# StepStick.net
KiCad netlist of a schematic drawn in Altium Designer
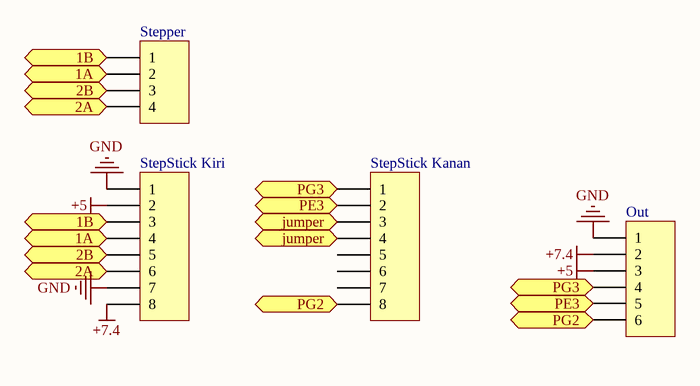
[diagram p0: StepStick.SchDoc]

(export (version "E")
  (design (tool "Eeschema 10.0.6"))
  (components
    (comp (ref "Out")
      (value "Header 6")
      (footprint "My_1X06")
      (description "Header, 6-Pin")
      (fields (field (name "PUBLISHER") "Altium Limited"))
      (libsource (lib "Mylib") (part "Header 6"))
    )
    (comp (ref "Stepper")
      (value "~")
      (footprint "My_1X04")
      (description "Header, 4-Pin")
      (fields (field (name "PUBLISHER") "Altium Limited"))
      (libsource (lib "Miscellaneous Connectors") (part "Header 4"))
    )
    (comp (ref "StepStick Kanan")
      (value "~")
      (footprint "HDR1X8")
      (description "Header, 8-Pin")
      (fields (field (name "PUBLISHER") "Altium Limited"))
      (libsource (lib "Miscellaneous Connectors") (part "Header 8"))
    )
    (comp (ref "StepStick Kiri")
      (value "~")
      (footprint "HDR1X8")
      (description "Header, 8-Pin")
      (fields (field (name "PUBLISHER") "Altium Limited"))
      (libsource (lib "Miscellaneous Connectors") (part "Header 8"))
    )
  )
  (nets
    (net (code "1") (name "+5") (class "Default")
      (node (ref "Out") (pin "3") (pinfunction "3_3") (pintype "passive"))
      (node (ref "StepStick Kiri") (pin "2") (pinfunction "2_2") (pintype "passive"))
    )
    (net (code "2") (name "+7.4") (class "Default")
      (node (ref "Out") (pin "2") (pinfunction "2_2") (pintype "passive"))
      (node (ref "StepStick Kiri") (pin "8") (pinfunction "8_8") (pintype "passive"))
    )
    (net (code "3") (name "/1A") (class "Default")
      (node (ref "StepStick Kiri") (pin "4") (pinfunction "4_4") (pintype "passive"))
      (node (ref "Stepper") (pin "2") (pinfunction "2_2") (pintype "passive"))
    )
    (net (code "4") (name "/1B") (class "Default")
      (node (ref "StepStick Kiri") (pin "3") (pinfunction "3_3") (pintype "passive"))
      (node (ref "Stepper") (pin "1") (pinfunction "1_1") (pintype "passive"))
    )
    (net (code "5") (name "/2A") (class "Default")
      (node (ref "StepStick Kiri") (pin "6") (pinfunction "6_6") (pintype "passive"))
      (node (ref "Stepper") (pin "4") (pinfunction "4_4") (pintype "passive"))
    )
    (net (code "6") (name "/2B") (class "Default")
      (node (ref "StepStick Kiri") (pin "5") (pinfunction "5_5") (pintype "passive"))
      (node (ref "Stepper") (pin "3") (pinfunction "3_3") (pintype "passive"))
    )
    (net (code "7") (name "/PE3") (class "Default")
      (node (ref "Out") (pin "5") (pinfunction "5_5") (pintype "passive"))
      (node (ref "StepStick Kanan") (pin "2") (pinfunction "2_2") (pintype "passive"))
    )
    (net (code "8") (name "/PG2") (class "Default")
      (node (ref "Out") (pin "6") (pinfunction "6_6") (pintype "passive"))
      (node (ref "StepStick Kanan") (pin "8") (pinfunction "8_8") (pintype "passive"))
    )
    (net (code "9") (name "/PG3") (class "Default")
      (node (ref "Out") (pin "4") (pinfunction "4_4") (pintype "passive"))
      (node (ref "StepStick Kanan") (pin "1") (pinfunction "1_1") (pintype "passive"))
    )
    (net (code "10") (name "/jumper") (class "Default")
      (node (ref "StepStick Kanan") (pin "3") (pinfunction "3_3") (pintype "passive"))
      (node (ref "StepStick Kanan") (pin "4") (pinfunction "4_4") (pintype "passive"))
    )
    (net (code "11") (name "GND") (class "Default")
      (node (ref "Out") (pin "1") (pinfunction "1_1") (pintype "passive"))
      (node (ref "StepStick Kiri") (pin "1") (pinfunction "1_1") (pintype "passive"))
      (node (ref "StepStick Kiri") (pin "7") (pinfunction "7_7") (pintype "passive"))
    )
    (net (code "12") (name "unconnected-(StepStick Kanan-Pad5)") (class "Default")
      (node (ref "StepStick Kanan") (pin "5") (pinfunction "5_5") (pintype "passive"))
    )
    (net (code "13") (name "unconnected-(StepStick Kanan-Pad6)") (class "Default")
      (node (ref "StepStick Kanan") (pin "6") (pinfunction "6_6") (pintype "passive"))
    )
    (net (code "14") (name "unconnected-(StepStick Kanan-Pad7)") (class "Default")
      (node (ref "StepStick Kanan") (pin "7") (pinfunction "7_7") (pintype "passive"))
    )
  )
)
